# G.net
KiCad netlist of a schematic drawn in Altium Designer
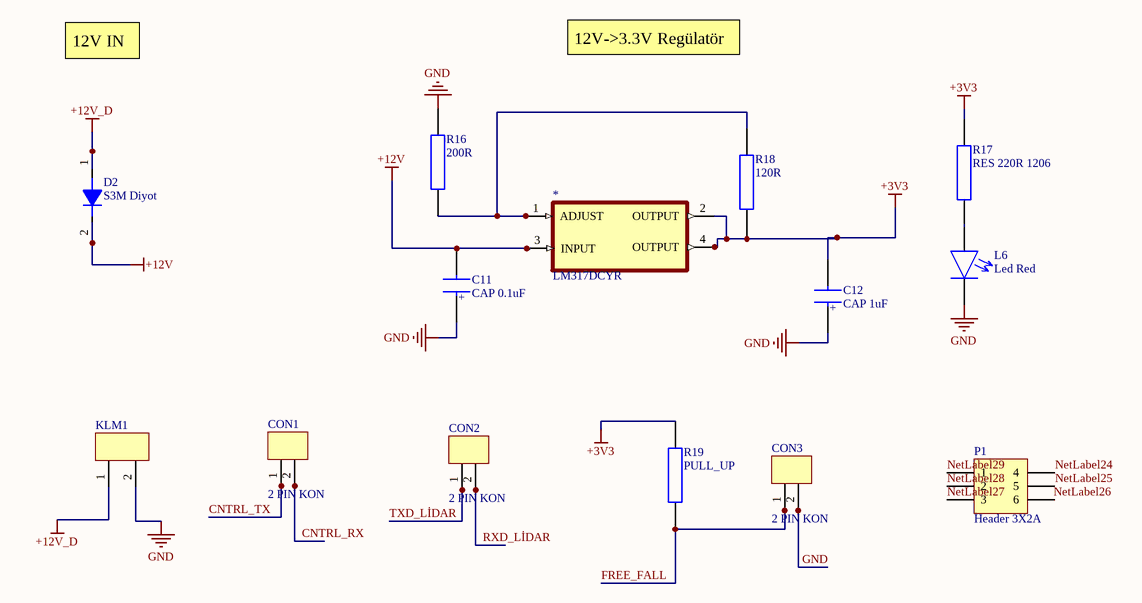
[diagram p0: Güç.SchDoc]

(export (version "E")
  (design (tool "Eeschema 10.0.6"))
  (components
    (comp (ref "*")
      (value "LM317DCYR")
      (footprint "SOT230P700X180-4N")
      (libsource (lib "Schlib") (part "LM317DCYR"))
    )
    (comp (ref "C11")
      (value "CAP 0.1uF")
      (footprint "CAP_805")
      (description "0805 smd")
      (libsource (lib "Udemy_Schlib1") (part "CAP 1uF"))
    )
    (comp (ref "C12")
      (value "CAP 1uF")
      (footprint "CAP_805")
      (description "0805 smd")
      (libsource (lib "Udemy_Schlib1") (part "CAP 1uF"))
    )
    (comp (ref "CON1")
      (value "2 PIN KON")
      (footprint "2 PIN 2.54MM")
      (description "2.54 mm vertical")
      (libsource (lib "Udemy_Schlib1") (part "2 PIN KON"))
    )
    (comp (ref "CON2")
      (value "2 PIN KON")
      (footprint "2 PIN 2.54MM")
      (description "2.54 mm vertical")
      (libsource (lib "Udemy_Schlib1") (part "2 PIN KON"))
    )
    (comp (ref "CON3")
      (value "2 PIN KON")
      (footprint "2 PIN 2.54MM")
      (description "2.54 mm vertical")
      (libsource (lib "Udemy_Schlib1") (part "2 PIN KON"))
    )
    (comp (ref "D2")
      (value "S3M Diyot")
      (footprint "DO214AA")
      (fields (field (name "VOLTAGE") "1000V"))
      (libsource (lib "Udemy_Schlib1") (part "S3M Diyot"))
    )
    (comp (ref "KLM1")
      (value "2 Pin Klemens")
      (footprint "5.08mm-2 pin")
      (description "5.08mm 2 pin klemens")
      (libsource (lib "Udemy_Schlib1") (part "2 Pin Klemens"))
    )
    (comp (ref "L6")
      (value "Led Red")
      (footprint "Led 1206")
      (libsource (lib "Udemy_Schlib1") (part "Led Red"))
    )
    (comp (ref "P1")
      (value "Header 3X2A")
      (footprint "HDR2X3_CEN")
      (description "Header, 3-Pin, Dual row")
      (fields (field (name "PUBLISHER") "Altium Limited"))
      (libsource (lib "Miscellaneous Connectors") (part "Header 3X2A"))
    )
    (comp (ref "R16")
      (value "200R")
      (footprint "RES_1206")
      (libsource (lib "Udemy_Schlib1") (part "RES 820R 1206"))
    )
    (comp (ref "R17")
      (value "RES 220R 1206")
      (footprint "RES_1206")
      (libsource (lib "Udemy_Schlib1") (part "RES 220R 1206"))
    )
    (comp (ref "R18")
      (value "120R")
      (footprint "RES_1206")
      (libsource (lib "Udemy_Schlib1") (part "RES 820R 1206"))
    )
    (comp (ref "R19")
      (value "PULL_UP")
      (footprint "RES_1206")
      (libsource (lib "Udemy_Schlib1") (part "RES 4.7K 1206"))
    )
  )
  (nets
    (net (code "1") (name "+3V3") (class "Default")
      (node (ref "*") (pin "2") (pinfunction "OUTPUT_2") (pintype "output"))
      (node (ref "*") (pin "4") (pinfunction "OUTPUT_4") (pintype "output"))
      (node (ref "C12") (pin "2") (pinfunction "2_2") (pintype "passive"))
      (node (ref "R17") (pin "2") (pintype "passive"))
      (node (ref "R18") (pin "2") (pintype "passive"))
      (node (ref "R19") (pin "2") (pintype "passive"))
    )
    (net (code "2") (name "+12V") (class "Default")
      (node (ref "*") (pin "3") (pinfunction "INPUT_3") (pintype "input"))
      (node (ref "C11") (pin "2") (pinfunction "2_2") (pintype "passive"))
      (node (ref "D2") (pin "2") (pintype "passive"))
    )
    (net (code "3") (name "+12V_D") (class "Default")
      (node (ref "D2") (pin "1") (pintype "passive"))
      (node (ref "KLM1") (pin "1") (pintype "passive"))
    )
    (net (code "5") (name "/CNTRL_RX") (class "Default") (node (ref "CON1") (pin "2") (pintype "passive")))
    (net (code "6") (name "/CNTRL_TX") (class "Default") (node (ref "CON1") (pin "1") (pintype "passive")))
    (net (code "7") (name "/FREE_FALL") (class "Default")
      (node (ref "CON3") (pin "1") (pintype "passive"))
      (node (ref "R19") (pin "1") (pintype "passive"))
    )
    (net (code "8") (name "/NetLabel24") (class "Default")
      (node (ref "P1") (pin "4") (pinfunction "4_4") (pintype "passive"))
    )
    (net (code "9") (name "/NetLabel25") (class "Default")
      (node (ref "P1") (pin "5") (pinfunction "5_5") (pintype "passive"))
    )
    (net (code "11") (name "/NetLabel27") (class "Default")
      (node (ref "P1") (pin "3") (pinfunction "3_3") (pintype "passive"))
    )
    (net (code "12") (name "/NetLabel28") (class "Default")
      (node (ref "P1") (pin "2") (pinfunction "2_2") (pintype "passive"))
    )
    (net (code "13") (name "/NetLabel29") (class "Default")
      (node (ref "P1") (pin "1") (pinfunction "1_1") (pintype "passive"))
    )
    (net (code "14") (name "/RXD_LİDAR") (class "Default") (node (ref "CON2") (pin "2") (pintype "passive")))
    (net (code "15") (name "/TXD_LİDAR") (class "Default") (node (ref "CON2") (pin "1") (pintype "passive")))
    (net (code "16") (name "GND") (class "Default")
      (node (ref "C11") (pin "1") (pinfunction "1_1") (pintype "passive"))
      (node (ref "C12") (pin "1") (pinfunction "1_1") (pintype "passive"))
      (node (ref "CON3") (pin "2") (pintype "passive"))
      (node (ref "KLM1") (pin "2") (pintype "passive"))
      (node (ref "L6") (pin "2") (pintype "passive"))
      (node (ref "R16") (pin "2") (pintype "passive"))
    )
    (net (code "17") (name "Net-(*-ADJUST)") (class "Default")
      (node (ref "*") (pin "1") (pinfunction "ADJUST_1") (pintype "input"))
      (node (ref "R16") (pin "1") (pintype "passive"))
      (node (ref "R18") (pin "1") (pintype "passive"))
    )
    (net (code "18") (name "Net-(L6-Pad1)") (class "Default")
      (node (ref "L6") (pin "1") (pintype "passive"))
      (node (ref "R17") (pin "1") (pintype "passive"))
    )
    (net (code "19") (name "unconnected-(P1-Pad6)") (class "Default")
      (node (ref "P1") (pin "6") (pinfunction "6_6") (pintype "passive"))
    )
  )
)
